# PAC_BDD_1.net
KiCad netlist of a schematic drawn in Altium Designer
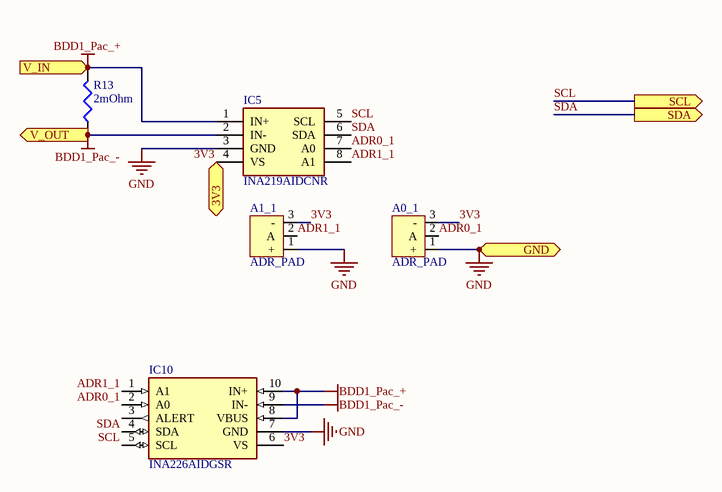
[diagram p0: PAC_BDD_1.SchDoc]

(export (version "E")
  (design (tool "Eeschema 10.0.6"))
  (components
    (comp (ref "A0_1")
      (value "ADR_PAD")
      (footprint "SOLDER_PAD")
      (description "ADR PAD 3 PIN")
      (libsource (lib "SCH_Aquatec") (part "ADR_PAD"))
    )
    (comp (ref "A1_1")
      (value "ADR_PAD")
      (footprint "SOLDER_PAD")
      (description "ADR PAD 3 PIN")
      (libsource (lib "SCH_Aquatec") (part "ADR_PAD"))
    )
    (comp (ref "IC5")
      (value "INA219AIDCNR")
      (footprint "SOT65P280X145-8N")
      (description "Integrated Circuit")
      (fields
        (field (name "MANUFACTURER_PART_NUMBER") "INA219BIDCNR")
        (field (name "MOUSER PART NUMBER") "595-INA219BIDCNR")
      )
      (libsource (lib "*") (part "INA219BIDCNR"))
    )
    (comp (ref "IC10")
      (value "INA226AIDGSR")
      (footprint "SamacSys:SOP50P490X110-10N")
      (description "Integrated Circuit")
      (fields (field (name "MOUSER PART NUMBER") "595-INA226AIDGSR"))
      (libsource (lib "*") (part "INA226AIDGSR"))
    )
    (comp (ref "R13")
      (value "2mOhm")
      (footprint "RESC3216X75N")
      (description "Resistor")
      (fields (field (name "PUBLISHER") "Altium Limited"))
      (libsource (lib "Miscellaneous Devices") (part "Res3"))
    )
  )
  (nets
    (net (code "1") (name "/3V3") (class "Default")
      (node (ref "A0_1") (pin "3") (pinfunction "-_3") (pintype "passive"))
      (node (ref "A1_1") (pin "3") (pinfunction "-_3") (pintype "passive"))
      (node (ref "IC10") (pin "6") (pinfunction "VS_6") (pintype "power_in"))
      (node (ref "IC5") (pin "4") (pinfunction "VS_4") (pintype "power_in"))
    )
    (net (code "2") (name "/ADR0_1") (class "Default")
      (node (ref "A0_1") (pin "2") (pinfunction "A_2") (pintype "passive"))
      (node (ref "IC10") (pin "2") (pinfunction "A0_2") (pintype "input"))
      (node (ref "IC5") (pin "7") (pinfunction "A0_7") (pintype "passive"))
    )
    (net (code "3") (name "/ADR1_1") (class "Default")
      (node (ref "A1_1") (pin "2") (pinfunction "A_2") (pintype "passive"))
      (node (ref "IC10") (pin "1") (pinfunction "A1_1") (pintype "input"))
      (node (ref "IC5") (pin "8") (pinfunction "A1_8") (pintype "passive"))
    )
    (net (code "4") (name "/SCL") (class "Default")
      (node (ref "IC10") (pin "5") (pinfunction "SCL_5") (pintype "bidirectional"))
      (node (ref "IC5") (pin "5") (pinfunction "SCL_5") (pintype "passive"))
    )
    (net (code "5") (name "/SDA") (class "Default")
      (node (ref "IC10") (pin "4") (pinfunction "SDA_4") (pintype "bidirectional"))
      (node (ref "IC5") (pin "6") (pinfunction "SDA_6") (pintype "passive"))
    )
    (net (code "6") (name "BDD1_Pac_+") (class "Default")
      (node (ref "IC10") (pin "10") (pinfunction "IN+_10") (pintype "input"))
      (node (ref "IC10") (pin "8") (pinfunction "VBUS_8") (pintype "input"))
      (node (ref "IC5") (pin "1") (pinfunction "IN+_1") (pintype "passive"))
      (node (ref "R13") (pin "2") (pinfunction "2_2") (pintype "passive"))
    )
    (net (code "7") (name "BDD1_Pac_-") (class "Default")
      (node (ref "IC10") (pin "9") (pinfunction "IN-_9") (pintype "input"))
      (node (ref "IC5") (pin "2") (pinfunction "IN-_2") (pintype "passive"))
      (node (ref "R13") (pin "1") (pinfunction "1_1") (pintype "passive"))
    )
    (net (code "8") (name "GND") (class "Default")
      (node (ref "A0_1") (pin "1") (pinfunction "+_1") (pintype "passive"))
      (node (ref "A1_1") (pin "1") (pinfunction "+_1") (pintype "passive"))
      (node (ref "IC10") (pin "7") (pinfunction "GND_7") (pintype "power_in"))
      (node (ref "IC5") (pin "3") (pinfunction "GND_3") (pintype "power_in"))
    )
    (net (code "9") (name "unconnected-(IC10-ALERT-Pad3)") (class "Default")
      (node (ref "IC10") (pin "3") (pinfunction "ALERT_3") (pintype "output"))
    )
  )
)
